# L293D.net
KiCad netlist of a schematic drawn in Altium Designer
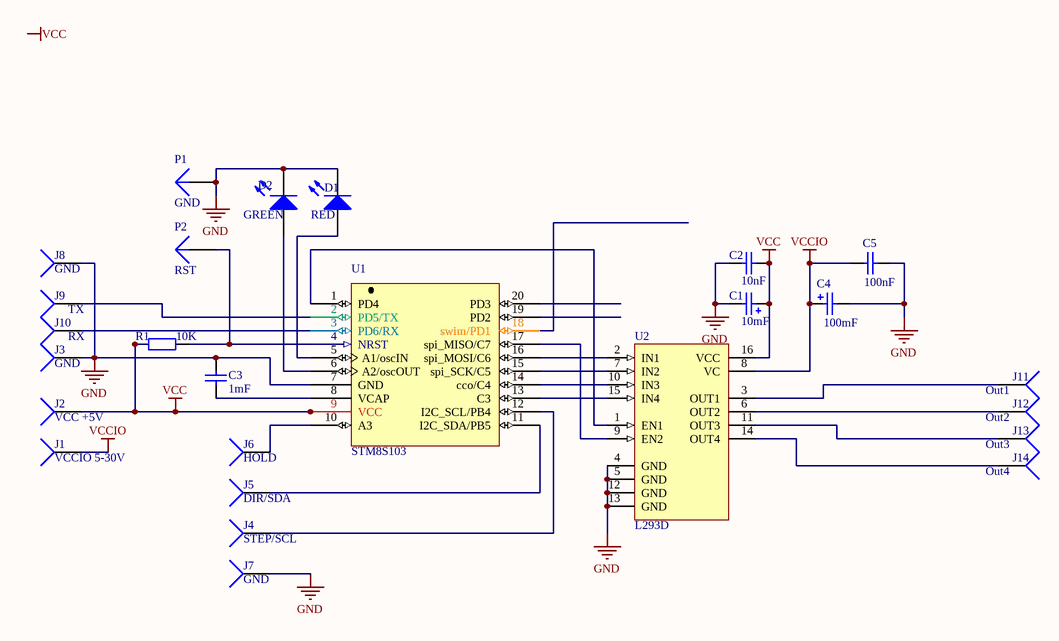
[diagram p0: L293D.SchDoc]

(export (version "E")
  (design (tool "Eeschema 10.0.6"))
  (components
    (comp (ref "C1")
      (value "10mF")
      (footprint "POLAR0.8")
      (description "Polarized Capacitor (Axial)")
      (fields (field (name "PUBLISHER") "Altium Limited"))
      (libsource (lib "Miscellaneous Devices") (part "Cap Pol2"))
    )
    (comp (ref "C2")
      (value "10nF")
      (footprint "RAD-0.3")
      (description "Capacitor")
      (fields (field (name "Comment") "Cap") (field (name "PUBLISHER") "Altium Limited"))
      (libsource (lib "Miscellaneous Devices") (part "Cap"))
    )
    (comp (ref "C3")
      (value "1mF")
      (footprint "RAD-0.3")
      (description "Capacitor")
      (fields (field (name "Comment") "Cap") (field (name "PUBLISHER") "Altium Limited"))
      (libsource (lib "Miscellaneous Devices") (part "Cap"))
    )
    (comp (ref "C4")
      (value "100mF")
      (footprint "POLAR0.8")
      (description "Polarized Capacitor (Axial)")
      (fields (field (name "PUBLISHER") "Altium Limited"))
      (libsource (lib "Miscellaneous Devices") (part "Cap Pol2"))
    )
    (comp (ref "C5")
      (value "100nF")
      (footprint "RAD-0.3")
      (description "Capacitor")
      (fields (field (name "Comment") "Cap") (field (name "PUBLISHER") "Altium Limited"))
      (libsource (lib "Miscellaneous Devices") (part "Cap"))
    )
    (comp (ref "D1")
      (value "RED")
      (footprint "3.5X2.8X1.9")
      (description "Typical BLUE SiC LED")
      (fields (field (name "PUBLISHER") "Altium Limited"))
      (libsource (lib "Miscellaneous Devices") (part "LED3"))
    )
    (comp (ref "D2")
      (value "GREEN")
      (footprint "3.5X2.8X1.9")
      (description "Typical BLUE SiC LED")
      (fields (field (name "PUBLISHER") "Altium Limited"))
      (libsource (lib "Miscellaneous Devices") (part "LED3"))
    )
    (comp (ref "J1")
      (value "VCCIO 5-30V")
      (footprint "PIN1")
      (description "Socket")
      (fields (field (name "PUBLISHER") "Altium Limited"))
      (libsource (lib "Miscellaneous Connectors") (part "Socket"))
    )
    (comp (ref "J2")
      (value "VCC +5V")
      (footprint "PIN1")
      (description "Socket")
      (fields (field (name "PUBLISHER") "Altium Limited"))
      (libsource (lib "Miscellaneous Connectors") (part "Socket"))
    )
    (comp (ref "J3")
      (value "GND")
      (footprint "PIN1")
      (description "Socket")
      (fields (field (name "PUBLISHER") "Altium Limited"))
      (libsource (lib "Miscellaneous Connectors") (part "Socket"))
    )
    (comp (ref "J4")
      (value "STEP/SCL")
      (footprint "PIN1")
      (description "Socket")
      (fields (field (name "PUBLISHER") "Altium Limited"))
      (libsource (lib "Miscellaneous Connectors") (part "Socket"))
    )
    (comp (ref "J5")
      (value "DIR/SDA")
      (footprint "PIN1")
      (description "Socket")
      (fields (field (name "PUBLISHER") "Altium Limited"))
      (libsource (lib "Miscellaneous Connectors") (part "Socket"))
    )
    (comp (ref "J6")
      (value "HOLD")
      (footprint "PIN1")
      (description "Socket")
      (fields (field (name "PUBLISHER") "Altium Limited"))
      (libsource (lib "Miscellaneous Connectors") (part "Socket"))
    )
    (comp (ref "J7")
      (value "GND")
      (footprint "PIN1")
      (description "Socket")
      (fields (field (name "PUBLISHER") "Altium Limited"))
      (libsource (lib "Miscellaneous Connectors") (part "Socket"))
    )
    (comp (ref "J8")
      (value "GND")
      (footprint "PIN1")
      (description "Socket")
      (fields (field (name "PUBLISHER") "Altium Limited"))
      (libsource (lib "Miscellaneous Connectors") (part "Socket"))
    )
    (comp (ref "J9")
      (value "TX")
      (footprint "PIN1")
      (description "Socket")
      (fields (field (name "PUBLISHER") "Altium Limited"))
      (libsource (lib "Miscellaneous Connectors") (part "Socket"))
    )
    (comp (ref "J10")
      (value "RX")
      (footprint "PIN1")
      (description "Socket")
      (fields (field (name "PUBLISHER") "Altium Limited"))
      (libsource (lib "Miscellaneous Connectors") (part "Socket"))
    )
    (comp (ref "J11")
      (value "Out1")
      (footprint "PIN1")
      (description "Socket")
      (fields (field (name "PUBLISHER") "Altium Limited"))
      (libsource (lib "Miscellaneous Connectors") (part "Socket"))
    )
    (comp (ref "J12")
      (value "Out2")
      (footprint "PIN1")
      (description "Socket")
      (fields (field (name "PUBLISHER") "Altium Limited"))
      (libsource (lib "Miscellaneous Connectors") (part "Socket"))
    )
    (comp (ref "J13")
      (value "Out3")
      (footprint "PIN1")
      (description "Socket")
      (fields (field (name "PUBLISHER") "Altium Limited"))
      (libsource (lib "Miscellaneous Connectors") (part "Socket"))
    )
    (comp (ref "J14")
      (value "Out4")
      (footprint "PIN1")
      (description "Socket")
      (fields (field (name "PUBLISHER") "Altium Limited"))
      (libsource (lib "Miscellaneous Connectors") (part "Socket"))
    )
    (comp (ref "P1")
      (value "GND")
      (footprint "PIN1")
      (description "Plug")
      (fields (field (name "PUBLISHER") "Altium Limited"))
      (libsource (lib "Miscellaneous Connectors") (part "Plug"))
    )
    (comp (ref "P2")
      (value "RST")
      (footprint "PIN1")
      (description "Plug")
      (fields (field (name "PUBLISHER") "Altium Limited"))
      (libsource (lib "Miscellaneous Connectors") (part "Plug"))
    )
    (comp (ref "R1")
      (value "10K")
      (footprint "AXIAL-0.4")
      (description "Resistor")
      (fields (field (name "Comment") "Res2") (field (name "PUBLISHER") "Altium Limited"))
      (libsource (lib "Miscellaneous Devices") (part "Res2"))
    )
    (comp (ref "U1") (value "STM8S103") (libsource (lib "STM8S") (part "STM8S103")))
    (comp (ref "U2")
      (value "L293D")
      (footprint "DIP16")
      (description "Push-Pull Four Channel Driver With Diode")
      (fields (field (name "PUBLISHER") "Altium Limited"))
      (libsource (lib "ST Interface DC & Stepper Motor Controller") (part "L293D"))
    )
  )
  (nets
    (net (code "1") (name "GND") (class "Default")
      (node (ref "C1") (pin "2") (pinfunction "2_2") (pintype "passive"))
      (node (ref "C2") (pin "2") (pinfunction "2_2") (pintype "passive"))
      (node (ref "C3") (pin "1") (pinfunction "1_1") (pintype "passive"))
      (node (ref "C4") (pin "2") (pinfunction "2_2") (pintype "passive"))
      (node (ref "C5") (pin "2") (pinfunction "2_2") (pintype "passive"))
      (node (ref "D1") (pin "2") (pinfunction "K_2") (pintype "passive"))
      (node (ref "D2") (pin "2") (pinfunction "K_2") (pintype "passive"))
      (node (ref "J3") (pin "1") (pinfunction "1_1") (pintype "passive"))
      (node (ref "J7") (pin "1") (pinfunction "1_1") (pintype "passive"))
      (node (ref "J8") (pin "1") (pinfunction "1_1") (pintype "passive"))
      (node (ref "P1") (pin "1") (pinfunction "1_1") (pintype "passive"))
      (node (ref "U1") (pin "7") (pinfunction "GND_7") (pintype "power_in"))
      (node (ref "U2") (pin "12") (pinfunction "GND_12") (pintype "power_in"))
      (node (ref "U2") (pin "13") (pinfunction "GND_13") (pintype "power_in"))
      (node (ref "U2") (pin "4") (pinfunction "GND_4") (pintype "power_in"))
      (node (ref "U2") (pin "5") (pinfunction "GND_5") (pintype "power_in"))
    )
    (net (code "2") (name "Net-(D1-A)") (class "Default")
      (node (ref "D1") (pin "1") (pinfunction "A_1") (pintype "passive"))
      (node (ref "U1") (pin "5") (pinfunction "A1/oscIN_5") (pintype "bidirectional"))
    )
    (net (code "3") (name "Net-(D2-A)") (class "Default")
      (node (ref "D2") (pin "1") (pinfunction "A_1") (pintype "passive"))
      (node (ref "U1") (pin "6") (pinfunction "A2/oscOUT_6") (pintype "bidirectional"))
    )
    (net (code "4") (name "Net-(U1-A3)") (class "Default")
      (node (ref "J6") (pin "1") (pinfunction "1_1") (pintype "passive"))
      (node (ref "U1") (pin "10") (pinfunction "A3_10") (pintype "bidirectional"))
    )
    (net (code "5") (name "Net-(U1-C3)") (class "Default")
      (node (ref "U1") (pin "13") (pinfunction "C3_13") (pintype "bidirectional"))
      (node (ref "U2") (pin "15") (pinfunction "IN4_15") (pintype "input"))
    )
    (net (code "6") (name "Net-(U1-I2C_SCL{slash}PB4)") (class "Default")
      (node (ref "J4") (pin "1") (pinfunction "1_1") (pintype "passive"))
      (node (ref "U1") (pin "12") (pinfunction "I2C_SCL/PB4_12") (pintype "bidirectional"))
    )
    (net (code "7") (name "Net-(U1-I2C_SDA{slash}PB5)") (class "Default")
      (node (ref "J5") (pin "1") (pinfunction "1_1") (pintype "passive"))
      (node (ref "U1") (pin "11") (pinfunction "I2C_SDA/PB5_11") (pintype "bidirectional"))
    )
    (net (code "8") (name "Net-(U1-NRST)") (class "Default")
      (node (ref "P2") (pin "1") (pinfunction "1_1") (pintype "passive"))
      (node (ref "R1") (pin "1") (pinfunction "1_1") (pintype "passive"))
      (node (ref "U1") (pin "4") (pinfunction "NRST_4") (pintype "input"))
    )
    (net (code "9") (name "Net-(U1-PD4)") (class "Default")
      (node (ref "U1") (pin "1") (pinfunction "PD4_1") (pintype "bidirectional"))
      (node (ref "U2") (pin "1") (pinfunction "EN1_1") (pintype "input"))
    )
    (net (code "10") (name "Net-(U1-PD5{slash}TX)") (class "Default")
      (node (ref "J9") (pin "1") (pinfunction "1_1") (pintype "passive"))
      (node (ref "U1") (pin "2") (pinfunction "PD5/TX_2") (pintype "bidirectional"))
    )
    (net (code "11") (name "Net-(U1-PD6{slash}RX)") (class "Default")
      (node (ref "J10") (pin "1") (pinfunction "1_1") (pintype "passive"))
      (node (ref "U1") (pin "3") (pinfunction "PD6/RX_3") (pintype "bidirectional"))
    )
    (net (code "12") (name "Net-(U1-VCAP)") (class "Default")
      (node (ref "C3") (pin "2") (pinfunction "2_2") (pintype "passive"))
      (node (ref "U1") (pin "8") (pinfunction "VCAP_8") (pintype "power_in"))
    )
    (net (code "13") (name "Net-(U1-cco{slash}C4)") (class "Default")
      (node (ref "U1") (pin "14") (pinfunction "cco/C4_14") (pintype "bidirectional"))
      (node (ref "U2") (pin "10") (pinfunction "IN3_10") (pintype "input"))
    )
    (net (code "14") (name "Net-(U1-spi_MISO{slash}C7)") (class "Default")
      (node (ref "U1") (pin "17") (pinfunction "spi_MISO/C7_17") (pintype "bidirectional"))
      (node (ref "U2") (pin "9") (pinfunction "EN2_9") (pintype "input"))
    )
    (net (code "15") (name "Net-(U1-spi_MOSI{slash}C6)") (class "Default")
      (node (ref "U1") (pin "16") (pinfunction "spi_MOSI/C6_16") (pintype "bidirectional"))
      (node (ref "U2") (pin "2") (pinfunction "IN1_2") (pintype "input"))
    )
    (net (code "16") (name "Net-(U1-spi_SCK{slash}C5)") (class "Default")
      (node (ref "U1") (pin "15") (pinfunction "spi_SCK/C5_15") (pintype "bidirectional"))
      (node (ref "U2") (pin "7") (pinfunction "IN2_7") (pintype "input"))
    )
    (net (code "17") (name "Net-(U2-OUT1)") (class "Default")
      (node (ref "J11") (pin "1") (pinfunction "1_1") (pintype "passive"))
      (node (ref "U2") (pin "3") (pinfunction "OUT1_3") (pintype "tri_state"))
    )
    (net (code "18") (name "Net-(U2-OUT2)") (class "Default")
      (node (ref "J12") (pin "1") (pinfunction "1_1") (pintype "passive"))
      (node (ref "U2") (pin "6") (pinfunction "OUT2_6") (pintype "tri_state"))
    )
    (net (code "19") (name "Net-(U2-OUT3)") (class "Default")
      (node (ref "J13") (pin "1") (pinfunction "1_1") (pintype "passive"))
      (node (ref "U2") (pin "11") (pinfunction "OUT3_11") (pintype "tri_state"))
    )
    (net (code "20") (name "Net-(U2-OUT4)") (class "Default")
      (node (ref "J14") (pin "1") (pinfunction "1_1") (pintype "passive"))
      (node (ref "U2") (pin "14") (pinfunction "OUT4_14") (pintype "tri_state"))
    )
    (net (code "21") (name "VCC") (class "Default")
      (node (ref "C1") (pin "1") (pinfunction "1_1") (pintype "passive"))
      (node (ref "C2") (pin "1") (pinfunction "1_1") (pintype "passive"))
      (node (ref "J2") (pin "1") (pinfunction "1_1") (pintype "passive"))
      (node (ref "R1") (pin "2") (pinfunction "2_2") (pintype "passive"))
      (node (ref "U1") (pin "9") (pinfunction "VCC_9") (pintype "power_in"))
      (node (ref "U2") (pin "16") (pinfunction "VCC_16") (pintype "power_in"))
    )
    (net (code "22") (name "VCCIO") (class "Default")
      (node (ref "C4") (pin "1") (pinfunction "1_1") (pintype "passive"))
      (node (ref "C5") (pin "1") (pinfunction "1_1") (pintype "passive"))
      (node (ref "J1") (pin "1") (pinfunction "1_1") (pintype "passive"))
      (node (ref "U2") (pin "8") (pinfunction "VC_8") (pintype "power_in"))
    )
    (net (code "23") (name "unconnected-(U1-PD2-Pad19)") (class "Default")
      (node (ref "U1") (pin "19") (pinfunction "PD2_19") (pintype "bidirectional"))
    )
    (net (code "24") (name "unconnected-(U1-PD3-Pad20)") (class "Default")
      (node (ref "U1") (pin "20") (pinfunction "PD3_20") (pintype "bidirectional"))
    )
    (net (code "25") (name "unconnected-(U1-swim{slash}PD1-Pad18)") (class "Default")
      (node (ref "U1") (pin "18") (pinfunction "swim/PD1_18") (pintype "bidirectional"))
    )
  )
)
